# reTerm-HW-M-IOLINK-STM32F4xx.net
KiCad netlist of a schematic drawn in Altium Designer
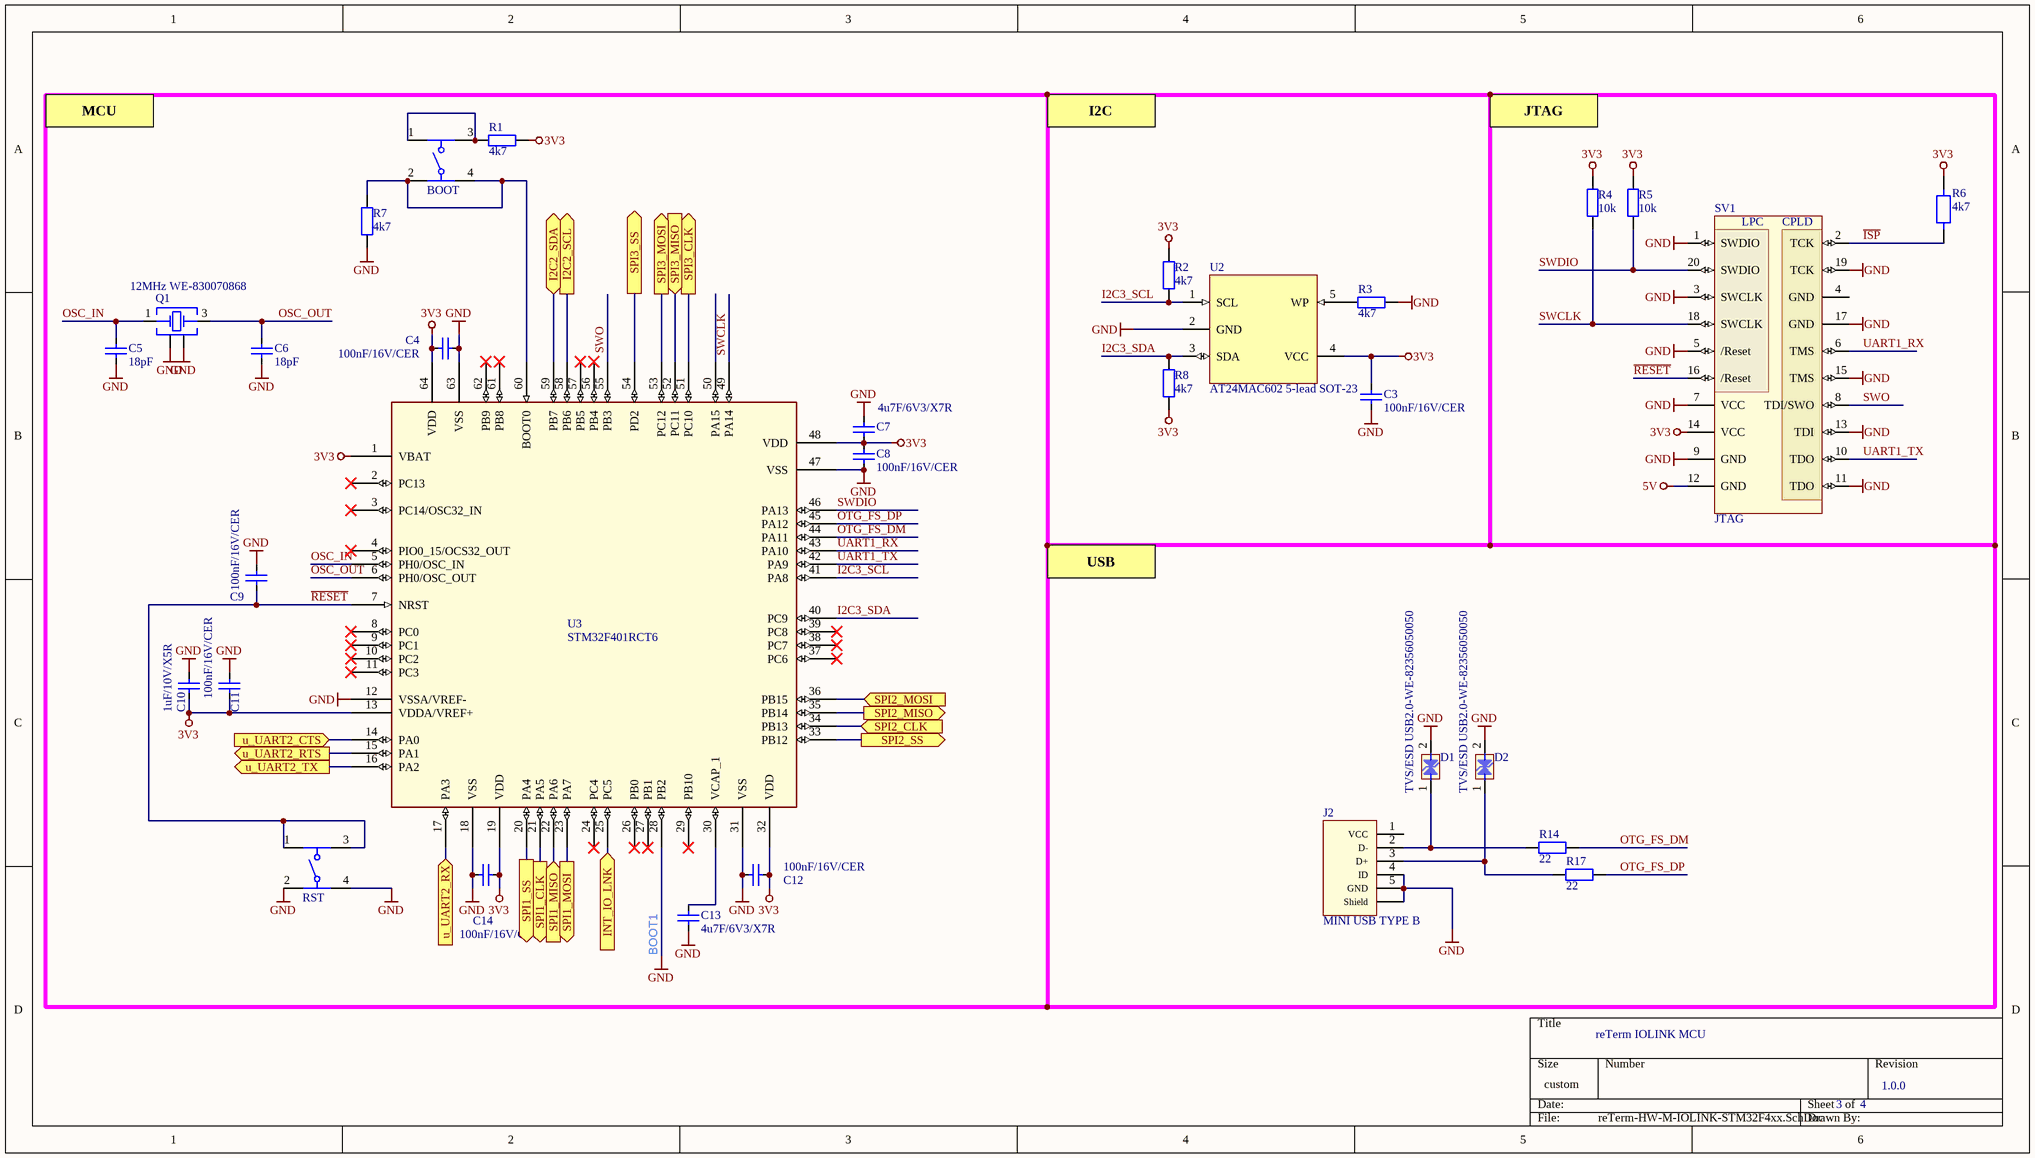
[diagram p0: reTerm-HW-M-IOLINK-STM32F4xx.SchDoc]

(export (version "E")
  (design (tool "Eeschema 10.0.6"))
  (components
    (comp (ref "BOOT")
      (value "WS-TASV J-BEND, 434153017835")
      (footprint "434153017835")
      (description "3.5x2.9mm SMD J-Bend WS-TASV, height 1.7 mm, 350 gf")
      (fields (field (name "PART NUMBER") "434153017835") (field (name "PUBLISHER") "Wurth Elektronik"))
      (libsource (lib "HE_Lib") (part "WS-TASV J-BEND, 434153017835"))
    )
    (comp (ref "C3")
      (value "100nF/16V/CER")
      (footprint "C0603")
      (libsource (lib "HE_Lib") (part "CAP_100nF_16V_CER"))
    )
    (comp (ref "C4")
      (value "100nF/16V/CER")
      (footprint "C0603")
      (libsource (lib "HE_Lib") (part "CAP_100nF_16V_CER"))
    )
    (comp (ref "C5") (value "18pF") (footprint "C0603") (libsource (lib "HE_Lib") (part "CAP_18pF")))
    (comp (ref "C6") (value "18pF") (footprint "C0603") (libsource (lib "HE_Lib") (part "CAP_18pF")))
    (comp (ref "C7")
      (value "4u7F/6V3/X7R")
      (footprint "C0603")
      (libsource (lib "HE_Lib") (part "CAP_4u7F/6V3/X7R"))
    )
    (comp (ref "C8")
      (value "100nF/16V/CER")
      (footprint "C0603")
      (libsource (lib "HE_Lib") (part "CAP_100nF_16V_CER"))
    )
    (comp (ref "C9")
      (value "100nF/16V/CER")
      (footprint "C0603")
      (libsource (lib "HE_Lib") (part "CAP_100nF_16V_CER"))
    )
    (comp (ref "C10")
      (value "1uF/10V/X5R")
      (footprint "C0603")
      (description "1uF/10V/X5R 0603")
      (libsource (lib "HE_Lib") (part "CAP_1uF/10V/X5R"))
    )
    (comp (ref "C11")
      (value "100nF/16V/CER")
      (footprint "C0603")
      (libsource (lib "HE_Lib") (part "CAP_100nF_16V_CER"))
    )
    (comp (ref "C12")
      (value "100nF/16V/CER")
      (footprint "C0603")
      (libsource (lib "HE_Lib") (part "CAP_100nF_16V_CER"))
    )
    (comp (ref "C13")
      (value "4u7F/6V3/X7R")
      (footprint "C0603")
      (libsource (lib "HE_Lib") (part "CAP_4u7F/6V3/X7R"))
    )
    (comp (ref "C14")
      (value "100nF/16V/CER")
      (footprint "C0603")
      (libsource (lib "HE_Lib") (part "CAP_100nF_16V_CER"))
    )
    (comp (ref "D1")
      (value "TVS/ESD USB2.0-WE-82356050050")
      (footprint "TVS/ESD_WE-VE_0603")
      (description "WE-VE ESD Suppressor, 0603, VDC=5V")
      (fields
        (field (name "PARTNO") "82356050050")
        (field (name "MANUFACTURER") "Wurth Elektronik")
        (field (name "CREATED BY") "BJ.Chen")
      )
      (libsource (lib "HE_Lib") (part "TVS/ESD USB2.0-WE-82356050050"))
    )
    (comp (ref "D2")
      (value "TVS/ESD USB2.0-WE-82356050050")
      (footprint "TVS/ESD_WE-VE_0603")
      (description "WE-VE ESD Suppressor, 0603, VDC=5V")
      (fields
        (field (name "PARTNO") "82356050050")
        (field (name "MANUFACTURER") "Wurth Elektronik")
        (field (name "CREATED BY") "BJ.Chen")
      )
      (libsource (lib "HE_Lib") (part "TVS/ESD USB2.0-WE-82356050050"))
    )
    (comp (ref "J2")
      (value "MINI USB TYPE B")
      (footprint "MINI USB WR 65100516121")
      (description "Mini USB 2.0 Type B SMT Horizontal 5 Contacts WR-COM")
      (fields (field (name "PART NUMBER") "65100516121") (field (name "PUBLISHER") "Wurth Elektronik"))
      (libsource (lib "HE_Lib") (part "MINI USB TYPE B"))
    )
    (comp (ref "Q1")
      (value "12MHz WE-830070868")
      (footprint "WE-XTAL_CFPX-180")
      (description "WE-XTAL Quartz Crystal, SMT, CFPX-180, 12MHz, +/-10ppm")
      (fields
        (field (name "MANUFACTURER PART NUMBER") "830070868")
        (field (name "MANUFACTURER") "Wurth Elektronik")
      )
      (libsource (lib "HE_Lib") (part "QUARTZ 22 MHZ - WE-830070868"))
    )
    (comp (ref "R1")
      (value "4k7")
      (footprint "R0603")
      (description "Resistor-4k7")
      (libsource (lib "HE_Lib") (part "R4k7"))
    )
    (comp (ref "R2")
      (value "4k7")
      (footprint "R0603")
      (description "Resistor-4k7")
      (libsource (lib "") (part "R4k7_1"))
    )
    (comp (ref "R3")
      (value "4k7")
      (footprint "R0603")
      (description "Resistor-4k7")
      (libsource (lib "HE_Lib") (part "R4k7"))
    )
    (comp (ref "R4")
      (value "10k")
      (footprint "R0603")
      (description "Resistor-10k")
      (libsource (lib "HE_Lib") (part "R10k"))
    )
    (comp (ref "R5")
      (value "10k")
      (footprint "R0603")
      (description "Resistor-10k")
      (libsource (lib "HE_Lib") (part "R10k"))
    )
    (comp (ref "R6")
      (value "4k7")
      (footprint "R0603")
      (description "Resistor")
      (libsource (lib "HE-Library") (part "RES2SS"))
    )
    (comp (ref "R7")
      (value "4k7")
      (footprint "R0603")
      (description "Resistor-4k7")
      (libsource (lib "") (part "R4k7_1"))
    )
    (comp (ref "R8")
      (value "4k7")
      (footprint "R0603")
      (description "Resistor-4k7")
      (libsource (lib "") (part "R4k7_1"))
    )
    (comp (ref "R14")
      (value "22")
      (footprint "R0603")
      (description "Resistor-22")
      (libsource (lib "HE_Lib") (part "R22"))
    )
    (comp (ref "R17")
      (value "22")
      (footprint "R0603")
      (description "Resistor-22")
      (libsource (lib "HE_Lib") (part "R22"))
    )
    (comp (ref "RST")
      (value "WS-TASV J-BEND, 434153017835")
      (footprint "434153017835")
      (description "3.5x2.9mm SMD J-Bend WS-TASV, height 1.7 mm, 350 gf")
      (fields (field (name "PART NUMBER") "434153017835") (field (name "PUBLISHER") "Wurth Elektronik"))
      (libsource (lib "HE_Lib") (part "WS-TASV J-BEND, 434153017835"))
    )
    (comp (ref "SV1")
      (value "JTAG")
      (footprint "JTAG-SAMTEC")
      (description "JTAG - Samtec Edgeconnector")
      (libsource (lib "HE_Lib") (part "JTAG-MSTKN"))
    )
    (comp (ref "U2")
      (value "AT24MAC602 5-lead SOT-23")
      (footprint "SOT23-5")
      (libsource (lib "HE_Lib") (part "AT24MAC602"))
    )
    (comp (ref "U3")
      (value "STM32F401RCT6")
      (footprint "LQFP64")
      (description "ARM  ®   Cortex  ®  -M4 32b MCU+FPU 256MB Flash 64KB RAM")
      (libsource (lib "HE_Lib") (part "STM32F401RCT6"))
    )
  )
  (nets
    (net (code "1") (name "/I2C2_SCL") (class "Default")
      (node (ref "U3") (pin "58") (pinfunction "PB6_58") (pintype "bidirectional"))
    )
    (net (code "2") (name "/I2C2_SDA") (class "Default")
      (node (ref "U3") (pin "59") (pinfunction "PB7_59") (pintype "bidirectional"))
    )
    (net (code "3") (name "/I2C3_SCL") (class "Default")
      (node (ref "R2") (pin "1") (pinfunction "1_1") (pintype "passive"))
      (node (ref "U2") (pin "1") (pinfunction "SCL_1") (pintype "input"))
      (node (ref "U3") (pin "41") (pinfunction "PA8_41") (pintype "bidirectional"))
    )
    (net (code "4") (name "/I2C3_SDA") (class "Default")
      (node (ref "R8") (pin "2") (pinfunction "2_2") (pintype "passive"))
      (node (ref "U2") (pin "3") (pinfunction "SDA_3") (pintype "bidirectional"))
      (node (ref "U3") (pin "40") (pinfunction "PC9_40") (pintype "bidirectional"))
    )
    (net (code "5") (name "/INT_IO_LNK") (class "Default")
      (node (ref "U3") (pin "25") (pinfunction "PC5_25") (pintype "bidirectional"))
    )
    (net (code "6") (name "/OSC_IN") (class "Default")
      (node (ref "C5") (pin "2") (pinfunction "2_2") (pintype "passive"))
      (node (ref "Q1") (pin "1") (pinfunction "Crystal_1") (pintype "passive"))
      (node (ref "U3") (pin "5") (pinfunction "PH0/OSC_IN_5") (pintype "bidirectional"))
    )
    (net (code "7") (name "/OSC_OUT") (class "Default")
      (node (ref "C6") (pin "2") (pinfunction "2_2") (pintype "passive"))
      (node (ref "Q1") (pin "3") (pinfunction "Crystal_3") (pintype "passive"))
      (node (ref "U3") (pin "6") (pinfunction "PH0/OSC_OUT_6") (pintype "bidirectional"))
    )
    (net (code "8") (name "/OTG_FS_DM") (class "Default")
      (node (ref "R14") (pin "2") (pinfunction "2_2") (pintype "passive"))
      (node (ref "U3") (pin "44") (pinfunction "PA11_44") (pintype "bidirectional"))
    )
    (net (code "9") (name "/OTG_FS_DP") (class "Default")
      (node (ref "R17") (pin "2") (pinfunction "2_2") (pintype "passive"))
      (node (ref "U3") (pin "45") (pinfunction "PA12_45") (pintype "bidirectional"))
    )
    (net (code "10") (name "/SPI1_CLK") (class "Default")
      (node (ref "U3") (pin "21") (pinfunction "PA5_21") (pintype "bidirectional"))
    )
    (net (code "11") (name "/SPI1_MISO") (class "Default")
      (node (ref "U3") (pin "22") (pinfunction "PA6_22") (pintype "bidirectional"))
    )
    (net (code "12") (name "/SPI1_MOSI") (class "Default")
      (node (ref "U3") (pin "23") (pinfunction "PA7_23") (pintype "bidirectional"))
    )
    (net (code "13") (name "/SPI1_SS") (class "Default")
      (node (ref "U3") (pin "20") (pinfunction "PA4_20") (pintype "bidirectional"))
    )
    (net (code "14") (name "/SPI2_CLK") (class "Default")
      (node (ref "U3") (pin "34") (pinfunction "PB13_34") (pintype "bidirectional"))
    )
    (net (code "15") (name "/SPI2_MISO") (class "Default")
      (node (ref "U3") (pin "35") (pinfunction "PB14_35") (pintype "bidirectional"))
    )
    (net (code "16") (name "/SPI2_MOSI") (class "Default")
      (node (ref "U3") (pin "36") (pinfunction "PB15_36") (pintype "bidirectional"))
    )
    (net (code "17") (name "/SPI2_SS") (class "Default")
      (node (ref "U3") (pin "33") (pinfunction "PB12_33") (pintype "bidirectional"))
    )
    (net (code "18") (name "/SPI3_CLK") (class "Default")
      (node (ref "U3") (pin "51") (pinfunction "PC10_51") (pintype "bidirectional"))
    )
    (net (code "19") (name "/SPI3_MISO") (class "Default")
      (node (ref "U3") (pin "52") (pinfunction "PC11_52") (pintype "bidirectional"))
    )
    (net (code "20") (name "/SPI3_MOSI") (class "Default")
      (node (ref "U3") (pin "53") (pinfunction "PC12_53") (pintype "bidirectional"))
    )
    (net (code "21") (name "/SPI3_SS") (class "Default")
      (node (ref "U3") (pin "54") (pinfunction "PD2_54") (pintype "bidirectional"))
    )
    (net (code "22") (name "/SWCLK") (class "Default")
      (node (ref "R4") (pin "1") (pinfunction "1_1") (pintype "passive"))
      (node (ref "SV1") (pin "18") (pinfunction "SWCLK_18") (pintype "bidirectional"))
      (node (ref "U3") (pin "49") (pinfunction "PA14_49") (pintype "bidirectional"))
    )
    (net (code "23") (name "/SWDIO") (class "Default")
      (node (ref "R5") (pin "1") (pinfunction "1_1") (pintype "passive"))
      (node (ref "SV1") (pin "20") (pinfunction "SWDIO_20") (pintype "bidirectional"))
      (node (ref "U3") (pin "46") (pinfunction "PA13_46") (pintype "bidirectional"))
    )
    (net (code "24") (name "/SWO") (class "Default")
      (node (ref "SV1") (pin "8") (pinfunction "TDI/SWO_8") (pintype "bidirectional"))
      (node (ref "U3") (pin "55") (pinfunction "PB3_55") (pintype "bidirectional"))
    )
    (net (code "25") (name "/UART1_RX") (class "Default")
      (node (ref "SV1") (pin "6") (pinfunction "TMS_6") (pintype "bidirectional"))
      (node (ref "U3") (pin "43") (pinfunction "PA10_43") (pintype "bidirectional"))
    )
    (net (code "26") (name "/UART1_TX") (class "Default")
      (node (ref "SV1") (pin "10") (pinfunction "TDO_10") (pintype "bidirectional"))
      (node (ref "U3") (pin "42") (pinfunction "PA9_42") (pintype "bidirectional"))
    )
    (net (code "27") (name "/u_UART2_CTS") (class "Default")
      (node (ref "U3") (pin "14") (pinfunction "PA0_14") (pintype "bidirectional"))
    )
    (net (code "28") (name "/u_UART2_RTS") (class "Default")
      (node (ref "U3") (pin "15") (pinfunction "PA1_15") (pintype "bidirectional"))
    )
    (net (code "29") (name "/u_UART2_RX") (class "Default")
      (node (ref "U3") (pin "17") (pinfunction "PA3_17") (pintype "bidirectional"))
    )
    (net (code "30") (name "/u_UART2_TX") (class "Default")
      (node (ref "U3") (pin "16") (pinfunction "PA2_16") (pintype "bidirectional"))
    )
    (net (code "31") (name "/~{ISP}") (class "Default")
      (node (ref "R6") (pin "2") (pinfunction "2_2") (pintype "passive"))
      (node (ref "SV1") (pin "2") (pinfunction "TCK_2") (pintype "bidirectional"))
    )
    (net (code "32") (name "/~{RESET}") (class "Default")
      (node (ref "C9") (pin "1") (pinfunction "1_1") (pintype "passive"))
      (node (ref "RST") (pin "1") (pinfunction "1_1") (pintype "passive"))
      (node (ref "RST") (pin "3") (pinfunction "3_3") (pintype "passive"))
      (node (ref "SV1") (pin "16") (pinfunction "/Reset_16") (pintype "bidirectional"))
      (node (ref "U3") (pin "7") (pinfunction "NRST_7") (pintype "input"))
    )
    (net (code "33") (name "3V3") (class "Default")
      (node (ref "C10") (pin "2") (pinfunction "2_2") (pintype "passive"))
      (node (ref "C11") (pin "1") (pinfunction "1_1") (pintype "passive"))
      (node (ref "C12") (pin "2") (pinfunction "2_2") (pintype "passive"))
      (node (ref "C14") (pin "2") (pinfunction "2_2") (pintype "passive"))
      (node (ref "C3") (pin "2") (pinfunction "2_2") (pintype "passive"))
      (node (ref "C4") (pin "1") (pinfunction "1_1") (pintype "passive"))
      (node (ref "C7") (pin "2") (pinfunction "2_2") (pintype "passive"))
      (node (ref "C8") (pin "2") (pinfunction "2_2") (pintype "passive"))
      (node (ref "R1") (pin "2") (pinfunction "2_2") (pintype "passive"))
      (node (ref "R2") (pin "2") (pinfunction "2_2") (pintype "passive"))
      (node (ref "R4") (pin "2") (pinfunction "2_2") (pintype "passive"))
      (node (ref "R5") (pin "2") (pinfunction "2_2") (pintype "passive"))
      (node (ref "R6") (pin "1") (pinfunction "1_1") (pintype "passive"))
      (node (ref "R8") (pin "1") (pinfunction "1_1") (pintype "passive"))
      (node (ref "SV1") (pin "14") (pinfunction "VCC_14") (pintype "power_in"))
      (node (ref "U2") (pin "4") (pinfunction "VCC_4") (pintype "power_in"))
      (node (ref "U3") (pin "1") (pinfunction "VBAT_1") (pintype "power_in"))
      (node (ref "U3") (pin "13") (pinfunction "VDDA/VREF+_13") (pintype "power_in"))
      (node (ref "U3") (pin "19") (pinfunction "VDD_19") (pintype "power_in"))
      (node (ref "U3") (pin "32") (pinfunction "VDD_32") (pintype "power_in"))
      (node (ref "U3") (pin "48") (pinfunction "VDD_48") (pintype "power_in"))
      (node (ref "U3") (pin "64") (pinfunction "VDD_64") (pintype "power_in"))
    )
    (net (code "34") (name "5V") (class "Default")
      (node (ref "SV1") (pin "12") (pinfunction "GND_12") (pintype "power_in"))
    )
    (net (code "35") (name "GND") (class "Default")
      (node (ref "C10") (pin "1") (pinfunction "1_1") (pintype "passive"))
      (node (ref "C11") (pin "2") (pinfunction "2_2") (pintype "passive"))
      (node (ref "C12") (pin "1") (pinfunction "1_1") (pintype "passive"))
      (node (ref "C13") (pin "1") (pinfunction "1_1") (pintype "passive"))
      (node (ref "C14") (pin "1") (pinfunction "1_1") (pintype "passive"))
      (node (ref "C3") (pin "1") (pinfunction "1_1") (pintype "passive"))
      (node (ref "C4") (pin "2") (pinfunction "2_2") (pintype "passive"))
      (node (ref "C5") (pin "1") (pinfunction "1_1") (pintype "passive"))
      (node (ref "C6") (pin "1") (pinfunction "1_1") (pintype "passive"))
      (node (ref "C7") (pin "1") (pinfunction "1_1") (pintype "passive"))
      (node (ref "C8") (pin "1") (pinfunction "1_1") (pintype "passive"))
      (node (ref "C9") (pin "2") (pinfunction "2_2") (pintype "passive"))
      (node (ref "D1") (pin "2") (pinfunction "I/O2_2") (pintype "passive"))
      (node (ref "D2") (pin "2") (pinfunction "I/O2_2") (pintype "passive"))
      (node (ref "J2") (pin "4") (pinfunction "ID_4") (pintype "passive"))
      (node (ref "J2") (pin "5") (pinfunction "GND_5") (pintype "passive"))
      (node (ref "J2") (pin "Shell") (pinfunction "Shield_Shell") (pintype "passive"))
      (node (ref "Q1") (pin "2") (pinfunction "GND_2") (pintype "passive"))
      (node (ref "Q1") (pin "4") (pinfunction "GND_4") (pintype "passive"))
      (node (ref "R3") (pin "2") (pinfunction "2_2") (pintype "passive"))
      (node (ref "R7") (pin "1") (pinfunction "1_1") (pintype "passive"))
      (node (ref "RST") (pin "2") (pinfunction "2_2") (pintype "passive"))
      (node (ref "RST") (pin "4") (pinfunction "4_4") (pintype "passive"))
      (node (ref "SV1") (pin "1") (pinfunction "SWDIO_1") (pintype "bidirectional"))
      (node (ref "SV1") (pin "11") (pinfunction "TDO_11") (pintype "bidirectional"))
      (node (ref "SV1") (pin "13") (pinfunction "TDI_13") (pintype "bidirectional"))
      (node (ref "SV1") (pin "15") (pinfunction "TMS_15") (pintype "bidirectional"))
      (node (ref "SV1") (pin "17") (pinfunction "GND_17") (pintype "power_in"))
      (node (ref "SV1") (pin "19") (pinfunction "TCK_19") (pintype "bidirectional"))
      (node (ref "SV1") (pin "3") (pinfunction "SWCLK_3") (pintype "bidirectional"))
      (node (ref "SV1") (pin "5") (pinfunction "/Reset_5") (pintype "bidirectional"))
      (node (ref "SV1") (pin "7") (pinfunction "VCC_7") (pintype "power_in"))
      (node (ref "SV1") (pin "9") (pinfunction "GND_9") (pintype "power_in"))
      (node (ref "U2") (pin "2") (pinfunction "GND_2") (pintype "power_in"))
      (node (ref "U3") (pin "12") (pinfunction "VSSA/VREF-_12") (pintype "power_in"))
      (node (ref "U3") (pin "18") (pinfunction "VSS_18") (pintype "power_in"))
      (node (ref "U3") (pin "28") (pinfunction "PB2_28") (pintype "bidirectional"))
      (node (ref "U3") (pin "31") (pinfunction "VSS_31") (pintype "power_in"))
      (node (ref "U3") (pin "47") (pinfunction "VSS_47") (pintype "power_in"))
      (node (ref "U3") (pin "63") (pinfunction "VSS_63") (pintype "power_in"))
    )
    (net (code "36") (name "Net-(BOOT-Pad1)") (class "Default")
      (node (ref "BOOT") (pin "1") (pinfunction "1_1") (pintype "passive"))
      (node (ref "BOOT") (pin "3") (pinfunction "3_3") (pintype "passive"))
      (node (ref "R1") (pin "1") (pinfunction "1_1") (pintype "passive"))
    )
    (net (code "37") (name "Net-(D1-I{slash}O1)") (class "Default")
      (node (ref "D1") (pin "1") (pinfunction "I/O1_1") (pintype "passive"))
      (node (ref "J2") (pin "2") (pinfunction "D-_2") (pintype "passive"))
      (node (ref "R14") (pin "1") (pinfunction "1_1") (pintype "passive"))
    )
    (net (code "38") (name "Net-(D2-I{slash}O1)") (class "Default")
      (node (ref "D2") (pin "1") (pinfunction "I/O1_1") (pintype "passive"))
      (node (ref "J2") (pin "3") (pinfunction "D+_3") (pintype "passive"))
      (node (ref "R17") (pin "1") (pinfunction "1_1") (pintype "passive"))
    )
    (net (code "39") (name "Net-(U2-WP)") (class "Default")
      (node (ref "R3") (pin "1") (pinfunction "1_1") (pintype "passive"))
      (node (ref "U2") (pin "5") (pinfunction "WP_5") (pintype "input"))
    )
    (net (code "40") (name "Net-(U3-BOOT0)") (class "Default")
      (node (ref "BOOT") (pin "2") (pinfunction "2_2") (pintype "passive"))
      (node (ref "BOOT") (pin "4") (pinfunction "4_4") (pintype "passive"))
      (node (ref "R7") (pin "2") (pinfunction "2_2") (pintype "passive"))
      (node (ref "U3") (pin "60") (pinfunction "BOOT0_60") (pintype "input"))
    )
    (net (code "41") (name "Net-(U3-VCAP_1)") (class "Default")
      (node (ref "C13") (pin "2") (pinfunction "2_2") (pintype "passive"))
      (node (ref "U3") (pin "30") (pinfunction "VCAP_1_30") (pintype "bidirectional"))
    )
    (net (code "42") (name "unconnected-(J2-VCC-Pad1)") (class "Default")
      (node (ref "J2") (pin "1") (pinfunction "VCC_1") (pintype "passive"))
    )
    (net (code "43") (name "unconnected-(SV1-GND-Pad4)") (class "Default")
      (node (ref "SV1") (pin "4") (pinfunction "GND_4") (pintype "power_in"))
    )
    (net (code "44") (name "unconnected-(U3-PA15-Pad50)") (class "Default")
      (node (ref "U3") (pin "50") (pinfunction "PA15_50") (pintype "bidirectional"))
    )
    (net (code "45") (name "unconnected-(U3-PB0-Pad26)") (class "Default")
      (node (ref "U3") (pin "26") (pinfunction "PB0_26") (pintype "bidirectional+no_connect"))
    )
    (net (code "46") (name "unconnected-(U3-PB1-Pad27)") (class "Default")
      (node (ref "U3") (pin "27") (pinfunction "PB1_27") (pintype "bidirectional+no_connect"))
    )
    (net (code "47") (name "unconnected-(U3-PB4-Pad56)") (class "Default")
      (node (ref "U3") (pin "56") (pinfunction "PB4_56") (pintype "bidirectional+no_connect"))
    )
    (net (code "48") (name "unconnected-(U3-PB5-Pad57)") (class "Default")
      (node (ref "U3") (pin "57") (pinfunction "PB5_57") (pintype "bidirectional+no_connect"))
    )
    (net (code "49") (name "unconnected-(U3-PB8-Pad61)") (class "Default")
      (node (ref "U3") (pin "61") (pinfunction "PB8_61") (pintype "bidirectional+no_connect"))
    )
    (net (code "50") (name "unconnected-(U3-PB9-Pad62)") (class "Default")
      (node (ref "U3") (pin "62") (pinfunction "PB9_62") (pintype "bidirectional+no_connect"))
    )
    (net (code "51") (name "unconnected-(U3-PB10-Pad29)") (class "Default")
      (node (ref "U3") (pin "29") (pinfunction "PB10_29") (pintype "bidirectional+no_connect"))
    )
    (net (code "52") (name "unconnected-(U3-PC0-Pad8)") (class "Default")
      (node (ref "U3") (pin "8") (pinfunction "PC0_8") (pintype "bidirectional+no_connect"))
    )
    (net (code "53") (name "unconnected-(U3-PC1-Pad9)") (class "Default")
      (node (ref "U3") (pin "9") (pinfunction "PC1_9") (pintype "bidirectional+no_connect"))
    )
    (net (code "54") (name "unconnected-(U3-PC2-Pad10)") (class "Default")
      (node (ref "U3") (pin "10") (pinfunction "PC2_10") (pintype "bidirectional+no_connect"))
    )
    (net (code "55") (name "unconnected-(U3-PC3-Pad11)") (class "Default")
      (node (ref "U3") (pin "11") (pinfunction "PC3_11") (pintype "bidirectional+no_connect"))
    )
    (net (code "56") (name "unconnected-(U3-PC4-Pad24)") (class "Default")
      (node (ref "U3") (pin "24") (pinfunction "PC4_24") (pintype "bidirectional+no_connect"))
    )
    (net (code "57") (name "unconnected-(U3-PC6-Pad37)") (class "Default")
      (node (ref "U3") (pin "37") (pinfunction "PC6_37") (pintype "bidirectional+no_connect"))
    )
    (net (code "58") (name "unconnected-(U3-PC7-Pad38)") (class "Default")
      (node (ref "U3") (pin "38") (pinfunction "PC7_38") (pintype "bidirectional+no_connect"))
    )
    (net (code "59") (name "unconnected-(U3-PC8-Pad39)") (class "Default")
      (node (ref "U3") (pin "39") (pinfunction "PC8_39") (pintype "bidirectional+no_connect"))
    )
    (net (code "60") (name "unconnected-(U3-PC13-Pad2)") (class "Default")
      (node (ref "U3") (pin "2") (pinfunction "PC13_2") (pintype "bidirectional+no_connect"))
    )
    (net (code "61") (name "unconnected-(U3-PC14{slash}OSC32_IN-Pad3)") (class "Default")
      (node (ref "U3") (pin "3") (pinfunction "PC14/OSC32_IN_3") (pintype "bidirectional+no_connect"))
    )
    (net (code "62") (name "unconnected-(U3-PIO0_15{slash}OCS32_OUT-Pad4)") (class "Default")
      (node (ref "U3") (pin "4") (pinfunction "PIO0_15/OCS32_OUT_4") (pintype "bidirectional+no_connect"))
    )
  )
)
